# 5V.net
KiCad netlist of a schematic drawn in Altium Designer
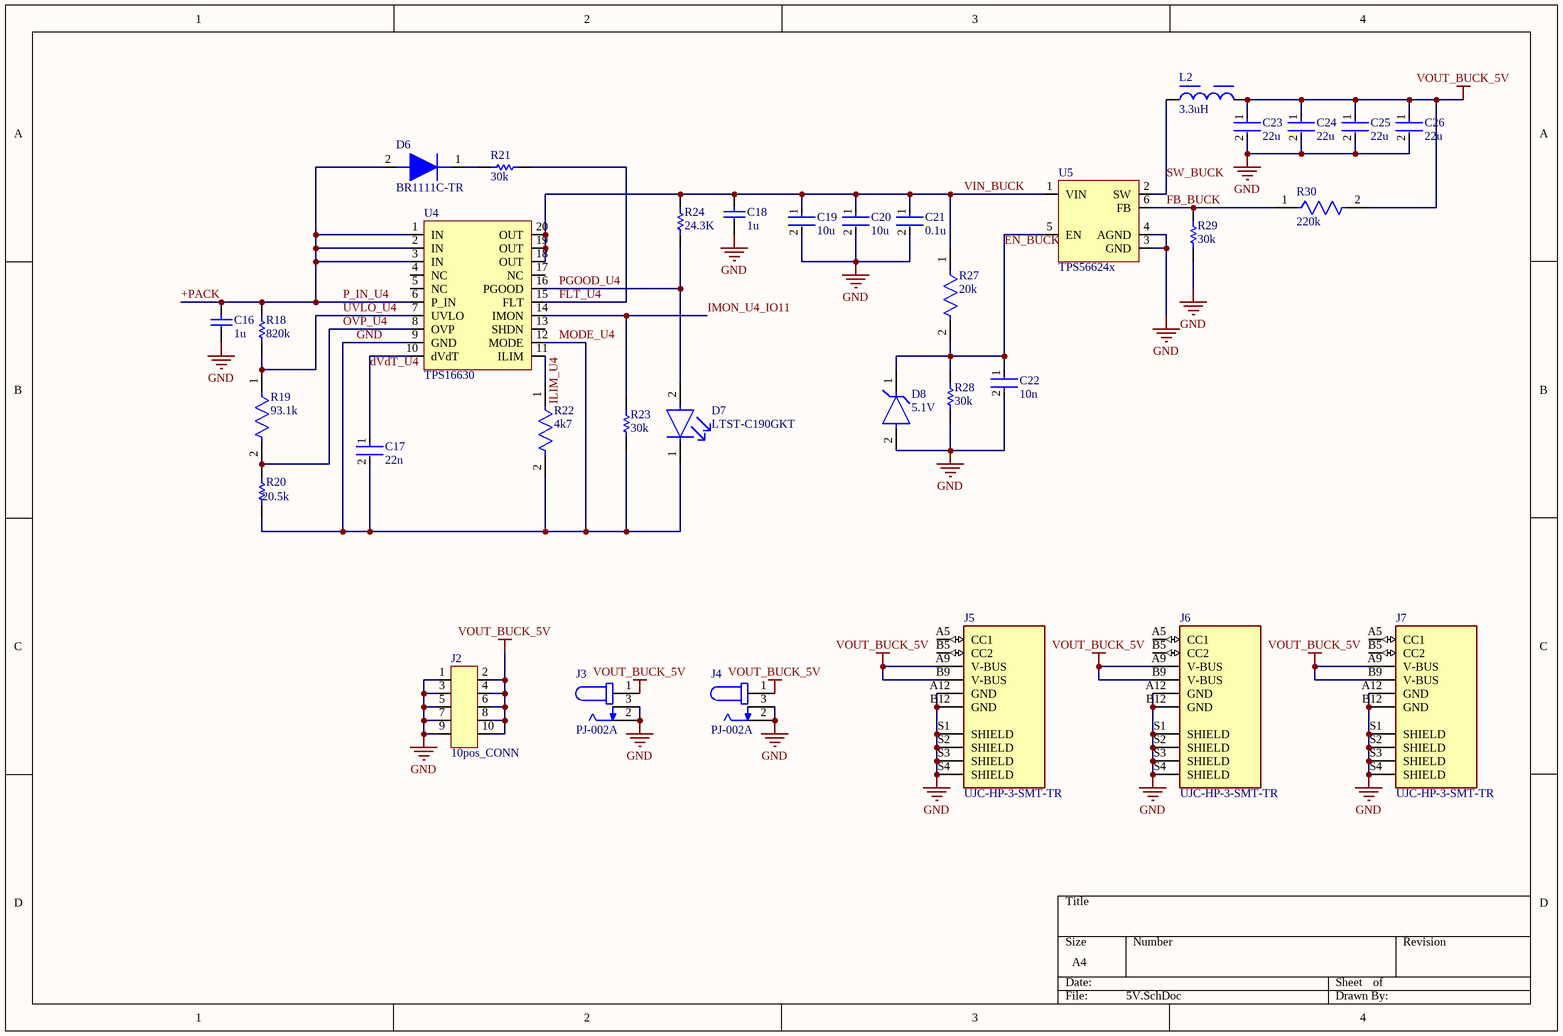
[diagram p0: 5V.SchDoc]

(export (version "E")
  (design (tool "Eeschema 10.0.6"))
  (components
    (comp (ref "C16")
      (value "1u")
      (footprint "CAPC2013X140X50ML20T25")
      (fields (field (name "MANUFACTURER") "Kemet") (field (name "PART NUMBER") "C0805C105K5RACTU"))
      (libsource (lib "Altium Content Vault") (part "CAP"))
    )
    (comp (ref "C17")
      (value "22n")
      (footprint "FP-C0603C-CF-MFG")
      (description "Ceramic Capacitor 0.022Uf 16V, X7R, 10%, 0603, Full Reel")
      (fields
        (field (name "OCTOPART") "https://octopart.com/c0603c223k4ractu-kemet-123286")
        (field (name "MANUFACTURER PART NUMBER") "C0603C223K4RACTU")
      )
      (libsource (lib "Altium Content Vault") (part "b4654b650e69147ec39a6b967a45e02"))
    )
    (comp (ref "C18")
      (value "1u")
      (footprint "CAPC2013X140X50ML20T25")
      (fields (field (name "MANUFACTURER") "Kemet") (field (name "PART NUMBER") "C0805C105K5RACTU"))
      (libsource (lib "Altium Content Vault") (part "CAP"))
    )
    (comp (ref "C19")
      (value "10u")
      (footprint "FP-GRM21B-0_15-IPC_A")
      (description "Chip Multilayer Ceramic Capacitors for General Purpose, 0805, 10uF, X5R, 15%, 20%, 25V")
      (fields (field (name "TOLERANCE") "20%"))
      (libsource (lib "Altium Content Vault") (part "b4654b650e69147ec39a6b967a45e02"))
    )
    (comp (ref "C20")
      (value "10u")
      (footprint "FP-GRM21B-0_15-IPC_A")
      (description "Chip Multilayer Ceramic Capacitors for General Purpose, 0805, 10uF, X5R, 15%, 20%, 25V")
      (fields (field (name "TOLERANCE") "20%"))
      (libsource (lib "Altium Content Vault") (part "b4654b650e69147ec39a6b967a45e02"))
    )
    (comp (ref "C21")
      (value "0.1u")
      (footprint "FP-C0603C-CF-MFG")
      (description "CAP CER 0.1UF 25V X7R 0603")
      (fields
        (field (name "OCTOPART") "https://octopart.com/c0603c104j3racauto-kemet-20761058")
        (field (name "MANUFACTURER") "KEMET")
      )
      (libsource (lib "Altium Content Vault") (part "b4654b650e69147ec39a6b967a45e02"))
    )
    (comp (ref "C22")
      (value "10n")
      (footprint "FP-C1608-080-0_1-MFG")
      (description "Multilayer Ceramic Capacitors 10nF ±10% 50V X7R SMD 0603")
      (fields (field (name "VOLTAGE") "50V") (field (name "TOLERANCE") "10%"))
      (libsource (lib "Altium Content Vault") (part "236180d848d6139a670b325ea6854c9"))
    )
    (comp (ref "C23")
      (value "22u")
      (footprint "FP-GRM21B-0_2-e0_2_0_7-IPC_C")
      (description "Chip Multilayer Ceramic Capacitors for General Purpose, 0805, 22uF, X5R, 15%, 20%, 10V")
      (fields (field (name "TOLERANCE") "20%") (field (name "VOLTAGE") "10V"))
      (libsource (lib "Altium Content Vault") (part "b4654b650e69147ec39a6b967a45e02"))
    )
    (comp (ref "C24")
      (value "22u")
      (footprint "FP-GRM21B-0_2-e0_2_0_7-IPC_C")
      (description "Chip Multilayer Ceramic Capacitors for General Purpose, 0805, 22uF, X5R, 15%, 20%, 10V")
      (fields (field (name "TOLERANCE") "20%") (field (name "VOLTAGE") "10V"))
      (libsource (lib "Altium Content Vault") (part "b4654b650e69147ec39a6b967a45e02"))
    )
    (comp (ref "C25")
      (value "22u")
      (footprint "FP-GRM21B-0_2-e0_2_0_7-IPC_C")
      (description "Chip Multilayer Ceramic Capacitors for General Purpose, 0805, 22uF, X5R, 15%, 20%, 10V")
      (fields (field (name "TOLERANCE") "20%") (field (name "VOLTAGE") "10V"))
      (libsource (lib "Altium Content Vault") (part "b4654b650e69147ec39a6b967a45e02"))
    )
    (comp (ref "C26")
      (value "22u")
      (footprint "FP-GRM21B-0_2-e0_2_0_7-IPC_C")
      (description "Chip Multilayer Ceramic Capacitors for General Purpose, 0805, 22uF, X5R, 15%, 20%, 10V")
      (fields (field (name "TOLERANCE") "20%") (field (name "VOLTAGE") "10V"))
      (libsource (lib "Altium Content Vault") (part "b4654b650e69147ec39a6b967a45e02"))
    )
    (comp (ref "D6")
      (value "BR1111C-TR")
      (footprint "LED_APHD1608LVBC/D")
      (libsource (lib "PowerDistribution") (part "BR1111C-TR"))
    )
    (comp (ref "D7")
      (value "LTST-C190GKT")
      (footprint "FP-LTST-C190GKT-MFG")
      (description "LED GREEN CLEAR CHIP SMD")
      (fields (field (name "VOLTAGE") "2V"))
      (libsource (lib "Altium Content Vault") (part "8706943c75ba83719d021d2fdc84c58"))
    )
    (comp (ref "D8")
      (value "5.1V")
      (footprint "FP-SOD123-MFG")
      (description "DIODE ZENER 5.1V 500MW SOD123")
      (fields
        (field (name "OCTOPART") "https://octopart.com/mmsz5231b-7-f-diodes+inc.-55400050")
        (field (name "MANUFACTURER") "Diodes")
      )
      (libsource (lib "Altium Content Vault") (part "f813f71cba58e380607f5dd3caf9714"))
    )
    (comp (ref "J2")
      (value "10pos_CONN")
      (footprint "61301021121")
      (libsource (lib "PowerDistribution") (part "10pos_CONN"))
    )
    (comp (ref "J3")
      (value "PJ-002A")
      (footprint "CUI_PJ-002A")
      (description "2.0 x 6.5 mm, 2.5 A, Horizontal, Through Hole, Dc Power Jack Connector")
      (fields (field (name "MF") "CUI Devices"))
      (libsource (lib "PowerDistribution") (part "PJ-002A"))
    )
    (comp (ref "J4")
      (value "PJ-002A")
      (footprint "CUI_PJ-002A")
      (description "2.0 x 6.5 mm, 2.5 A, Horizontal, Through Hole, Dc Power Jack Connector")
      (fields (field (name "MF") "CUI Devices"))
      (libsource (lib "PowerDistribution") (part "PJ-002A"))
    )
    (comp (ref "J5")
      (value "UJC-HP-3-SMT-TR")
      (footprint "CUI_UJC-HP-3-SMT-TR")
      (description "Type C, 3 A, Right Angle, Surface Mount (SMT), Power-Only USB Receptacle")
      (libsource (lib "PowerDistribution") (part "UJC-HP-3-SMT-TR"))
    )
    (comp (ref "J6")
      (value "UJC-HP-3-SMT-TR")
      (footprint "CUI_UJC-HP-3-SMT-TR")
      (description "Type C, 3 A, Right Angle, Surface Mount (SMT), Power-Only USB Receptacle")
      (libsource (lib "PowerDistribution") (part "UJC-HP-3-SMT-TR"))
    )
    (comp (ref "J7")
      (value "UJC-HP-3-SMT-TR")
      (footprint "CUI_UJC-HP-3-SMT-TR")
      (description "Type C, 3 A, Right Angle, Surface Mount (SMT), Power-Only USB Receptacle")
      (libsource (lib "PowerDistribution") (part "UJC-HP-3-SMT-TR"))
    )
    (comp (ref "L2")
      (value "3.3uH")
      (footprint "WE-HCI_1050")
      (fields (field (name "TOLERANCE") "20%"))
      (libsource (lib "Altium Content Vault") (part "Inductor - 3"))
    )
    (comp (ref "R18")
      (value "820k")
      (footprint "RESC1608X55X30ML15T15")
      (fields (field (name "MANUFACTURER") "Panasonic") (field (name "PART NUMBER") "ERJ3EKF8203V"))
      (libsource (lib "Altium Content Vault") (part "RES"))
    )
    (comp (ref "R19")
      (value "93.1k")
      (footprint "FP-CR0805-IPC_B")
      (description "Thick Film Chip Resistors 0805 93.1kΩ 0.125W 1% 100ppm/°C")
      (fields (field (name "TOLERANCE") "1%"))
      (libsource (lib "Altium Content Vault") (part "1029c3af85768c4190bb7ad29bc67b5"))
    )
    (comp (ref "R20")
      (value "20.5k")
      (footprint "RESC2013X60X40LL20T25")
      (fields (field (name "MANUFACTURER") "Panasonic") (field (name "PART NUMBER") "ERA6AEB2052V"))
      (libsource (lib "Altium Content Vault") (part "RES"))
    )
    (comp (ref "R21")
      (value "30k")
      (footprint "RESC1609X50X30ML10T20")
      (fields (field (name "MANUFACTURER") "Vishay Dale") (field (name "PART NUMBER") "CRCW060330K0JNEA"))
      (libsource (lib "Altium Content Vault") (part "RES"))
    )
    (comp (ref "R22")
      (value "4k7")
      (footprint "FP-RC1206-0_65-IPC_B")
      (description "RES SMD 4.7K OHM 1% 1/4W 1206")
      (fields (field (name "TOLERANCE") "1%"))
      (libsource (lib "Altium Content Vault") (part "1029c3af85768c4190bb7ad29bc67b5"))
    )
    (comp (ref "R23")
      (value "30k")
      (footprint "RESC1609X50X30ML10T20")
      (fields (field (name "MANUFACTURER") "Vishay Dale") (field (name "PART NUMBER") "CRCW060330K0JNEA"))
      (libsource (lib "Altium Content Vault") (part "RES"))
    )
    (comp (ref "R24")
      (value "24.3K")
      (footprint "RESC1609X50X30NL10T20")
      (fields (field (name "PART NUMBER") "CRCW060324K3FKEA") (field (name "MANUFACTURER") "Vishay Dale"))
      (libsource (lib "Altium Content Vault") (part "RES"))
    )
    (comp (ref "R27")
      (value "20k")
      (footprint "FP-CRCW0603-e3-IPC_C")
      (description "RES Thick Film, 20kΩ, 1%, 0.1W, 100ppm/°C, 0603")
      (fields (field (name "TOLERANCE") "1%"))
      (libsource (lib "Altium Content Vault") (part "1029c3af85768c4190bb7ad29bc67b5"))
    )
    (comp (ref "R28")
      (value "30k")
      (footprint "RESC1609X50X30LL10T20")
      (fields (field (name "PART NUMBER") "CRCW060330K0FKEA") (field (name "MANUFACTURER") "Vishay Dale"))
      (libsource (lib "Altium Content Vault") (part "RES"))
    )
    (comp (ref "R29")
      (value "30k")
      (footprint "RESC1609X50X30LL10T20")
      (fields (field (name "PART NUMBER") "CRCW060330K0FKEA") (field (name "MANUFACTURER") "Vishay Dale"))
      (libsource (lib "Altium Content Vault") (part "RES"))
    )
    (comp (ref "R30")
      (value "220k")
      (footprint "FP-CRCW0603-HPe3-IPC_C")
      (description "RES Thick Film, 220kΩ, 1%, 0.33W, 100ppm/°C, 0603")
      (fields (field (name "TOLERANCE") "1%"))
      (libsource (lib "Altium Content Vault") (part "1029c3af85768c4190bb7ad29bc67b5"))
    )
    (comp (ref "U4")
      (value "TPS16630")
      (footprint "SOP65P640X110-21N")
      (libsource (lib "PowerDistribution") (part "TPS16630"))
    )
    (comp (ref "U5")
      (value "TPS56624x")
      (footprint "SOT23_6pin")
      (libsource (lib "PowerDistribution") (part "TPS56624x"))
    )
  )
  (nets
    (net (code "1") (name "/+PACK") (class "Default")
      (node (ref "C16") (pin "2") (pinfunction "2_2") (pintype "passive"))
      (node (ref "D6") (pin "2") (pinfunction "2_2") (pintype "passive"))
      (node (ref "R18") (pin "2") (pinfunction "2_2") (pintype "passive"))
      (node (ref "U4") (pin "1") (pinfunction "IN_1") (pintype "passive"))
      (node (ref "U4") (pin "2") (pinfunction "IN_2") (pintype "passive"))
      (node (ref "U4") (pin "3") (pinfunction "IN_3") (pintype "passive"))
      (node (ref "U4") (pin "6") (pinfunction "P_IN_6") (pintype "passive"))
    )
    (net (code "2") (name "/EN_BUCK") (class "Default")
      (node (ref "C22") (pin "1") (pinfunction "1_1") (pintype "passive"))
      (node (ref "D8") (pin "1") (pinfunction "C_1") (pintype "passive"))
      (node (ref "R27") (pin "2") (pinfunction "2_2") (pintype "passive"))
      (node (ref "R28") (pin "2") (pinfunction "2_2") (pintype "passive"))
      (node (ref "U5") (pin "5") (pinfunction "EN_5") (pintype "passive"))
    )
    (net (code "3") (name "/FB_BUCK") (class "Default")
      (node (ref "R29") (pin "2") (pinfunction "2_2") (pintype "passive"))
      (node (ref "R30") (pin "1") (pinfunction "1_1") (pintype "passive"))
      (node (ref "U5") (pin "6") (pinfunction "FB_6") (pintype "passive"))
    )
    (net (code "4") (name "/FLT_U4") (class "Default")
      (node (ref "R21") (pin "1") (pinfunction "1_1") (pintype "passive"))
      (node (ref "U4") (pin "15") (pinfunction "FLT_15") (pintype "passive"))
    )
    (net (code "5") (name "/ILIM_U4") (class "Default")
      (node (ref "R22") (pin "1") (pinfunction "1_1") (pintype "passive"))
      (node (ref "U4") (pin "11") (pinfunction "ILIM_11") (pintype "passive"))
    )
    (net (code "6") (name "/IMON_U4_IO11") (class "Default")
      (node (ref "R23") (pin "2") (pinfunction "2_2") (pintype "passive"))
      (node (ref "U4") (pin "14") (pinfunction "IMON_14") (pintype "passive"))
    )
    (net (code "7") (name "/OVP_U4") (class "Default")
      (node (ref "R19") (pin "2") (pinfunction "2_2") (pintype "passive"))
      (node (ref "R20") (pin "2") (pinfunction "2_2") (pintype "passive"))
      (node (ref "U4") (pin "8") (pinfunction "OVP_8") (pintype "passive"))
    )
    (net (code "8") (name "/PGOOD_U4") (class "Default")
      (node (ref "D7") (pin "2") (pinfunction "A_2") (pintype "passive"))
      (node (ref "R24") (pin "1") (pinfunction "1_1") (pintype "passive"))
      (node (ref "U4") (pin "16") (pinfunction "PGOOD_16") (pintype "passive"))
    )
    (net (code "9") (name "/SW_BUCK") (class "Default")
      (node (ref "L2") (pin "1") (pinfunction "1_1") (pintype "passive"))
      (node (ref "U5") (pin "2") (pinfunction "SW_2") (pintype "passive"))
    )
    (net (code "10") (name "/UVLO_U4") (class "Default")
      (node (ref "R18") (pin "1") (pinfunction "1_1") (pintype "passive"))
      (node (ref "R19") (pin "1") (pinfunction "1_1") (pintype "passive"))
      (node (ref "U4") (pin "7") (pinfunction "UVLO_7") (pintype "passive"))
    )
    (net (code "11") (name "/VIN_BUCK") (class "Default")
      (node (ref "C18") (pin "2") (pinfunction "2_2") (pintype "passive"))
      (node (ref "C19") (pin "1") (pinfunction "1_1") (pintype "passive"))
      (node (ref "C20") (pin "1") (pinfunction "1_1") (pintype "passive"))
      (node (ref "C21") (pin "1") (pinfunction "1_1") (pintype "passive"))
      (node (ref "R24") (pin "2") (pinfunction "2_2") (pintype "passive"))
      (node (ref "R27") (pin "1") (pinfunction "1_1") (pintype "passive"))
      (node (ref "U4") (pin "18") (pinfunction "OUT_18") (pintype "passive"))
      (node (ref "U4") (pin "19") (pinfunction "OUT_19") (pintype "passive"))
      (node (ref "U4") (pin "20") (pinfunction "OUT_20") (pintype "passive"))
      (node (ref "U5") (pin "1") (pinfunction "VIN_1") (pintype "passive"))
    )
    (net (code "12") (name "/dVdT_U4") (class "Default")
      (node (ref "C17") (pin "1") (pinfunction "1_1") (pintype "passive"))
      (node (ref "U4") (pin "10") (pinfunction "dVdT_10") (pintype "passive"))
    )
    (net (code "13") (name "GND") (class "Default")
      (node (ref "C16") (pin "1") (pinfunction "1_1") (pintype "passive"))
      (node (ref "C17") (pin "2") (pinfunction "2_2") (pintype "passive"))
      (node (ref "C18") (pin "1") (pinfunction "1_1") (pintype "passive"))
      (node (ref "C19") (pin "2") (pinfunction "2_2") (pintype "passive"))
      (node (ref "C20") (pin "2") (pinfunction "2_2") (pintype "passive"))
      (node (ref "C21") (pin "2") (pinfunction "2_2") (pintype "passive"))
      (node (ref "C22") (pin "2") (pinfunction "2_2") (pintype "passive"))
      (node (ref "C23") (pin "2") (pinfunction "2_2") (pintype "passive"))
      (node (ref "C24") (pin "2") (pinfunction "2_2") (pintype "passive"))
      (node (ref "C25") (pin "2") (pinfunction "2_2") (pintype "passive"))
      (node (ref "C26") (pin "2") (pinfunction "2_2") (pintype "passive"))
      (node (ref "D7") (pin "1") (pinfunction "C_1") (pintype "passive"))
      (node (ref "D8") (pin "2") (pinfunction "A_2") (pintype "passive"))
      (node (ref "J2") (pin "1") (pintype "passive"))
      (node (ref "J2") (pin "3") (pintype "passive"))
      (node (ref "J2") (pin "5") (pintype "passive"))
      (node (ref "J2") (pin "7") (pintype "passive"))
      (node (ref "J2") (pin "9") (pintype "passive"))
      (node (ref "J3") (pin "2") (pinfunction "2_2") (pintype "passive"))
      (node (ref "J3") (pin "3") (pinfunction "3_3") (pintype "passive"))
      (node (ref "J4") (pin "2") (pinfunction "2_2") (pintype "passive"))
      (node (ref "J4") (pin "3") (pinfunction "3_3") (pintype "passive"))
      (node (ref "J5") (pin "A12") (pinfunction "GND_A12") (pintype "power_in"))
      (node (ref "J5") (pin "B12") (pinfunction "GND_B12") (pintype "power_in"))
      (node (ref "J5") (pin "S1") (pinfunction "SHIELD_S1") (pintype "passive"))
      (node (ref "J5") (pin "S2") (pinfunction "SHIELD_S2") (pintype "passive"))
      (node (ref "J5") (pin "S3") (pinfunction "SHIELD_S3") (pintype "passive"))
      (node (ref "J5") (pin "S4") (pinfunction "SHIELD_S4") (pintype "passive"))
      (node (ref "J6") (pin "A12") (pinfunction "GND_A12") (pintype "power_in"))
      (node (ref "J6") (pin "B12") (pinfunction "GND_B12") (pintype "power_in"))
      (node (ref "J6") (pin "S1") (pinfunction "SHIELD_S1") (pintype "passive"))
      (node (ref "J6") (pin "S2") (pinfunction "SHIELD_S2") (pintype "passive"))
      (node (ref "J6") (pin "S3") (pinfunction "SHIELD_S3") (pintype "passive"))
      (node (ref "J6") (pin "S4") (pinfunction "SHIELD_S4") (pintype "passive"))
      (node (ref "J7") (pin "A12") (pinfunction "GND_A12") (pintype "power_in"))
      (node (ref "J7") (pin "B12") (pinfunction "GND_B12") (pintype "power_in"))
      (node (ref "J7") (pin "S1") (pinfunction "SHIELD_S1") (pintype "passive"))
      (node (ref "J7") (pin "S2") (pinfunction "SHIELD_S2") (pintype "passive"))
      (node (ref "J7") (pin "S3") (pinfunction "SHIELD_S3") (pintype "passive"))
      (node (ref "J7") (pin "S4") (pinfunction "SHIELD_S4") (pintype "passive"))
      (node (ref "R20") (pin "1") (pinfunction "1_1") (pintype "passive"))
      (node (ref "R22") (pin "2") (pinfunction "2_2") (pintype "passive"))
      (node (ref "R23") (pin "1") (pinfunction "1_1") (pintype "passive"))
      (node (ref "R28") (pin "1") (pinfunction "1_1") (pintype "passive"))
      (node (ref "R29") (pin "1") (pinfunction "1_1") (pintype "passive"))
      (node (ref "U4") (pin "12") (pinfunction "MODE_12") (pintype "passive"))
      (node (ref "U4") (pin "9") (pinfunction "GND_9") (pintype "passive"))
      (node (ref "U5") (pin "3") (pinfunction "GND_3") (pintype "passive"))
      (node (ref "U5") (pin "4") (pinfunction "AGND_4") (pintype "passive"))
    )
    (net (code "14") (name "Net-(D6-Pad1)") (class "Default")
      (node (ref "D6") (pin "1") (pinfunction "1_1") (pintype "passive"))
      (node (ref "R21") (pin "2") (pinfunction "2_2") (pintype "passive"))
    )
    (net (code "15") (name "VOUT_BUCK_5V") (class "Default")
      (node (ref "C23") (pin "1") (pinfunction "1_1") (pintype "passive"))
      (node (ref "C24") (pin "1") (pinfunction "1_1") (pintype "passive"))
      (node (ref "C25") (pin "1") (pinfunction "1_1") (pintype "passive"))
      (node (ref "C26") (pin "1") (pinfunction "1_1") (pintype "passive"))
      (node (ref "J2") (pin "10") (pintype "passive"))
      (node (ref "J2") (pin "2") (pintype "passive"))
      (node (ref "J2") (pin "4") (pintype "passive"))
      (node (ref "J2") (pin "6") (pintype "passive"))
      (node (ref "J2") (pin "8") (pintype "passive"))
      (node (ref "J3") (pin "1") (pinfunction "1_1") (pintype "passive"))
      (node (ref "J4") (pin "1") (pinfunction "1_1") (pintype "passive"))
      (node (ref "J5") (pin "A9") (pinfunction "V-BUS_A9") (pintype "power_in"))
      (node (ref "J5") (pin "B9") (pinfunction "V-BUS_B9") (pintype "power_in"))
      (node (ref "J6") (pin "A9") (pinfunction "V-BUS_A9") (pintype "power_in"))
      (node (ref "J6") (pin "B9") (pinfunction "V-BUS_B9") (pintype "power_in"))
      (node (ref "J7") (pin "A9") (pinfunction "V-BUS_A9") (pintype "power_in"))
      (node (ref "J7") (pin "B9") (pinfunction "V-BUS_B9") (pintype "power_in"))
      (node (ref "L2") (pin "2") (pinfunction "2_2") (pintype "passive"))
      (node (ref "R30") (pin "2") (pinfunction "2_2") (pintype "passive"))
    )
    (net (code "16") (name "unconnected-(J5-CC1-PadA5)") (class "Default")
      (node (ref "J5") (pin "A5") (pinfunction "CC1_A5") (pintype "bidirectional"))
    )
    (net (code "17") (name "unconnected-(J5-CC2-PadB5)") (class "Default")
      (node (ref "J5") (pin "B5") (pinfunction "CC2_B5") (pintype "bidirectional"))
    )
    (net (code "18") (name "unconnected-(J6-CC1-PadA5)") (class "Default")
      (node (ref "J6") (pin "A5") (pinfunction "CC1_A5") (pintype "bidirectional"))
    )
    (net (code "19") (name "unconnected-(J6-CC2-PadB5)") (class "Default")
      (node (ref "J6") (pin "B5") (pinfunction "CC2_B5") (pintype "bidirectional"))
    )
    (net (code "20") (name "unconnected-(J7-CC1-PadA5)") (class "Default")
      (node (ref "J7") (pin "A5") (pinfunction "CC1_A5") (pintype "bidirectional"))
    )
    (net (code "21") (name "unconnected-(J7-CC2-PadB5)") (class "Default")
      (node (ref "J7") (pin "B5") (pinfunction "CC2_B5") (pintype "bidirectional"))
    )
    (net (code "22") (name "unconnected-(U4-NC-Pad4)") (class "Default")
      (node (ref "U4") (pin "4") (pinfunction "NC_4") (pintype "passive"))
    )
    (net (code "23") (name "unconnected-(U4-NC-Pad5)") (class "Default")
      (node (ref "U4") (pin "5") (pinfunction "NC_5") (pintype "passive"))
    )
    (net (code "24") (name "unconnected-(U4-NC-Pad17)") (class "Default")
      (node (ref "U4") (pin "17") (pinfunction "NC_17") (pintype "passive"))
    )
    (net (code "25") (name "unconnected-(U4-SHDN-Pad13)") (class "Default")
      (node (ref "U4") (pin "13") (pinfunction "SHDN_13") (pintype "passive"))
    )
  )
)
